# sensor.net
KiCad netlist of a schematic drawn in Altium Designer
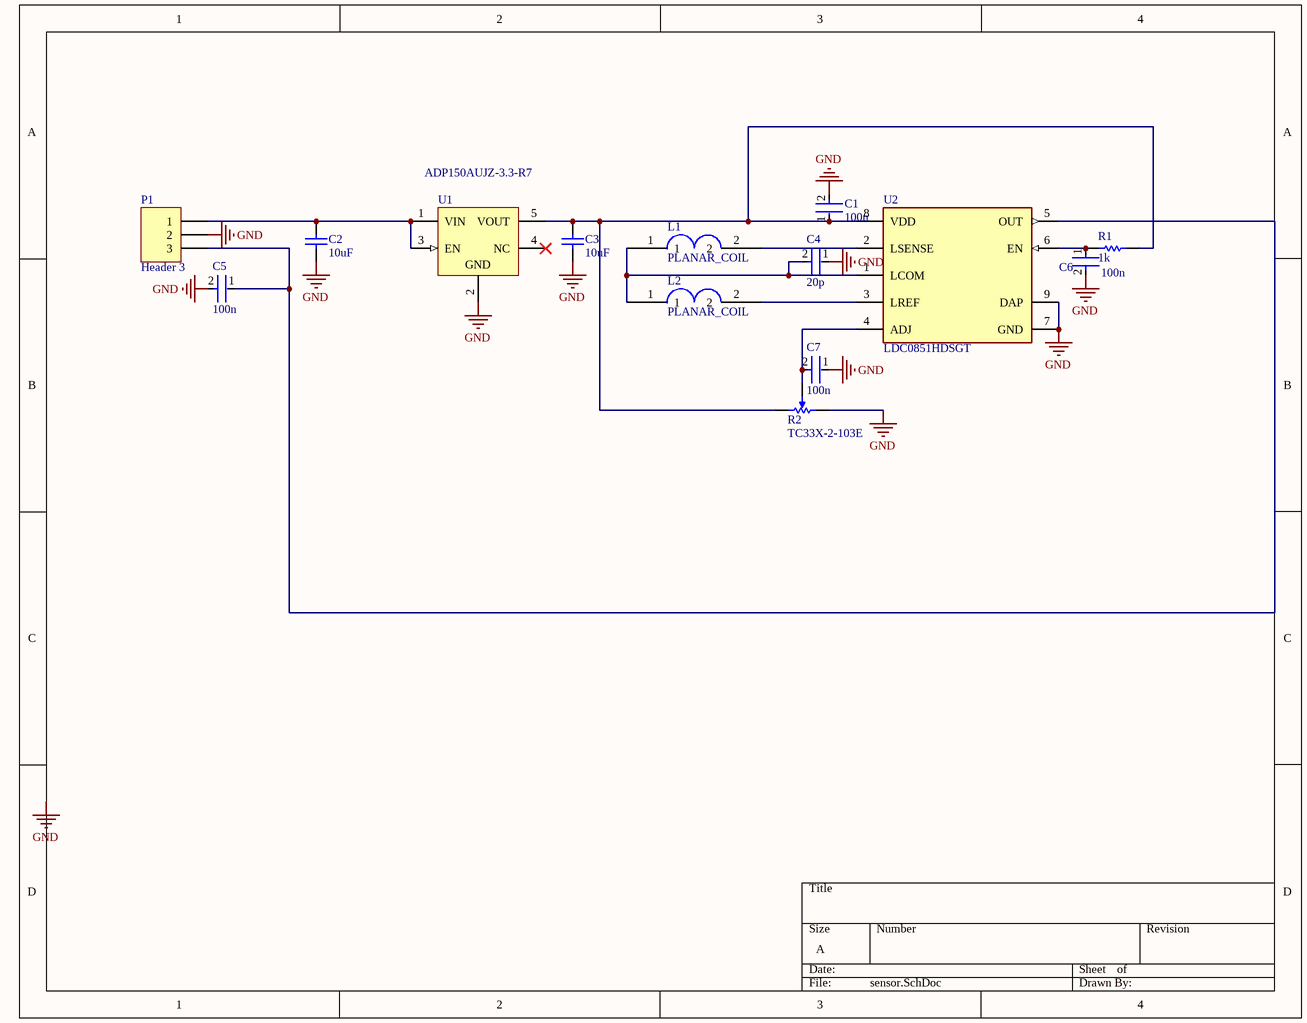
[diagram p0: sensor.SchDoc]

(export (version "E")
  (design (tool "Eeschema 10.0.6"))
  (components
    (comp (ref "C1")
      (value "100n")
      (footprint "FP-GRM15-MFG")
      (description "CAP CER 0.1UF 16V X7R 0402")
      (fields (field (name "MANUFACTURER PART NUMBER") "GRM155R71C104KA88D") (field (name "TOLERANCE") "10%"))
      (libsource (lib "Altium Content Vault") (part "236180d848d6139a670b325ea6854c9"))
    )
    (comp (ref "C2")
      (value "10uF")
      (footprint "CAPC2013X94X50ML20T25")
      (fields
        (field (name "MANUFACTURER") "AVX Interconnect / Elco")
        (field (name "PART NUMBER") "08051C104JAT2A")
      )
      (libsource (lib "Altium Content Vault") (part "CAP"))
    )
    (comp (ref "C3")
      (value "10uF")
      (footprint "CAPC2013X94X50ML20T25")
      (fields
        (field (name "MANUFACTURER") "AVX Interconnect / Elco")
        (field (name "PART NUMBER") "08051C104JAT2A")
      )
      (libsource (lib "Altium Content Vault") (part "CAP"))
    )
    (comp (ref "C4")
      (value "20p")
      (footprint "FP-GRM15-MFG")
      (description "CAP CER 0.1UF 16V X7R 0402")
      (fields (field (name "MANUFACTURER PART NUMBER") "GRM155R71C104KA88D") (field (name "TOLERANCE") "10%"))
      (libsource (lib "Altium Content Vault") (part "236180d848d6139a670b325ea6854c9"))
    )
    (comp (ref "C5")
      (value "100n")
      (footprint "FP-GRM15-MFG")
      (description "CAP CER 0.1UF 16V X7R 0402")
      (fields (field (name "MANUFACTURER PART NUMBER") "GRM155R71C104KA88D") (field (name "TOLERANCE") "10%"))
      (libsource (lib "Altium Content Vault") (part "236180d848d6139a670b325ea6854c9"))
    )
    (comp (ref "C6")
      (value "100n")
      (footprint "FP-GRM15-MFG")
      (description "CAP CER 0.1UF 16V X7R 0402")
      (fields (field (name "MANUFACTURER PART NUMBER") "GRM155R71C104KA88D") (field (name "TOLERANCE") "10%"))
      (libsource (lib "Altium Content Vault") (part "236180d848d6139a670b325ea6854c9"))
    )
    (comp (ref "C7")
      (value "100n")
      (footprint "FP-GRM15-MFG")
      (description "CAP CER 0.1UF 16V X7R 0402")
      (fields (field (name "MANUFACTURER PART NUMBER") "GRM155R71C104KA88D") (field (name "TOLERANCE") "10%"))
      (libsource (lib "Altium Content Vault") (part "236180d848d6139a670b325ea6854c9"))
    )
    (comp (ref "L1")
      (value "PLANAR_COIL")
      (footprint "PLANAR_INDUCTOR")
      (libsource (lib "planar_coil") (part "PLANAR_COIL"))
    )
    (comp (ref "L2")
      (value "PLANAR_COIL")
      (footprint "PLANAR_INDUCTOR")
      (libsource (lib "planar_coil") (part "PLANAR_COIL"))
    )
    (comp (ref "P1")
      (value "Header 3")
      (footprint "HDR1X3")
      (description "Header, 3-Pin")
      (fields (field (name "PUBLISHER") "Altium Limited"))
      (libsource (lib "Miscellaneous Connectors") (part "Header 3"))
    )
    (comp (ref "R1")
      (value "1k")
      (footprint "RESC1005X40X25NL05T10")
      (fields (field (name "MANUFACTURER") "Yageo / Phycomp") (field (name "PART NUMBER") "RC0402JR-070RL"))
      (libsource (lib "Altium Content Vault") (part "RES"))
    )
    (comp (ref "R2")
      (value "TC33X-2-103E")
      (footprint "BOUR-TC33X-2_V")
      (description "Trimming Potentiometer, 10000 Ohm, -40 to 100 degC, 3-Pin SMD, RoHS, Tape and Reel")
      (fields (field (name "TOLERANCE") "25%") (field (name "MANUFACTURER") "Bourns"))
      (libsource (lib "Altium Content Vault") (part "RES-ADJ-3_A"))
    )
    (comp (ref "U1")
      (value "ADP150AUJZ-3.3-R7")
      (footprint "ADI-UJ-5_M")
      (fields (field (name "MANUFACTURER") "Analog Devices"))
      (libsource (lib "Altium Content Vault") (part "ADI-ADP1XX-UJ-5"))
    )
    (comp (ref "U2")
      (value "LDC0851HDSGT")
      (footprint "FP-DSG0008A-MFG")
      (description "SENSOR PROX INDUCTIVE 8WFDFN")
      (libsource (lib "Altium Content Vault") (part "7aa8b213d4fc0aa2c2f3e23343721e9"))
    )
  )
  (nets
    (net (code "1") (name "GND") (class "Default")
      (node (ref "C1") (pin "2") (pinfunction "2_2") (pintype "passive"))
      (node (ref "C2") (pin "1") (pinfunction "1_1") (pintype "passive"))
      (node (ref "C3") (pin "1") (pinfunction "1_1") (pintype "passive"))
      (node (ref "C4") (pin "1") (pinfunction "1_1") (pintype "passive"))
      (node (ref "C5") (pin "2") (pinfunction "2_2") (pintype "passive"))
      (node (ref "C6") (pin "2") (pinfunction "2_2") (pintype "passive"))
      (node (ref "C7") (pin "1") (pinfunction "1_1") (pintype "passive"))
      (node (ref "P1") (pin "2") (pinfunction "2_2") (pintype "passive"))
      (node (ref "R2") (pin "1") (pinfunction "1_1") (pintype "passive"))
      (node (ref "U1") (pin "2") (pinfunction "GND_2") (pintype "power_in"))
      (node (ref "U2") (pin "7") (pinfunction "GND_7") (pintype "power_in"))
      (node (ref "U2") (pin "9") (pinfunction "DAP_9") (pintype "power_in"))
    )
    (net (code "2") (name "Net-(U1-EN)") (class "Default")
      (node (ref "C2") (pin "2") (pinfunction "2_2") (pintype "passive"))
      (node (ref "P1") (pin "1") (pinfunction "1_1") (pintype "passive"))
      (node (ref "U1") (pin "1") (pinfunction "VIN_1") (pintype "power_in"))
      (node (ref "U1") (pin "3") (pinfunction "EN_3") (pintype "input"))
    )
    (net (code "3") (name "Net-(U1-VOUT)") (class "Default")
      (node (ref "C1") (pin "1") (pinfunction "1_1") (pintype "passive"))
      (node (ref "C3") (pin "2") (pinfunction "2_2") (pintype "passive"))
      (node (ref "R1") (pin "2") (pinfunction "2_2") (pintype "passive"))
      (node (ref "R2") (pin "3") (pinfunction "3_3") (pintype "passive"))
      (node (ref "U1") (pin "5") (pinfunction "VOUT_5") (pintype "power_in"))
      (node (ref "U2") (pin "8") (pinfunction "VDD_8") (pintype "power_in"))
    )
    (net (code "4") (name "Net-(U2-ADJ)") (class "Default")
      (node (ref "C7") (pin "2") (pinfunction "2_2") (pintype "passive"))
      (node (ref "R2") (pin "2") (pinfunction "2_2") (pintype "passive"))
      (node (ref "U2") (pin "4") (pinfunction "ADJ_4") (pintype "passive"))
    )
    (net (code "5") (name "Net-(U2-EN)") (class "Default")
      (node (ref "C6") (pin "1") (pinfunction "1_1") (pintype "passive"))
      (node (ref "R1") (pin "1") (pinfunction "1_1") (pintype "passive"))
      (node (ref "U2") (pin "6") (pinfunction "EN_6") (pintype "input"))
    )
    (net (code "6") (name "Net-(U2-LCOM)") (class "Default")
      (node (ref "C4") (pin "2") (pinfunction "2_2") (pintype "passive"))
      (node (ref "L1") (pin "1") (pinfunction "1_1") (pintype "passive"))
      (node (ref "L2") (pin "1") (pinfunction "1_1") (pintype "passive"))
      (node (ref "U2") (pin "1") (pinfunction "LCOM_1") (pintype "passive"))
    )
    (net (code "7") (name "Net-(U2-LREF)") (class "Default")
      (node (ref "L2") (pin "2") (pinfunction "2_2") (pintype "passive"))
      (node (ref "U2") (pin "3") (pinfunction "LREF_3") (pintype "passive"))
    )
    (net (code "8") (name "Net-(U2-LSENSE)") (class "Default")
      (node (ref "L1") (pin "2") (pinfunction "2_2") (pintype "passive"))
      (node (ref "U2") (pin "2") (pinfunction "LSENSE_2") (pintype "passive"))
    )
    (net (code "9") (name "Net-(U2-OUT)") (class "Default")
      (node (ref "C5") (pin "1") (pinfunction "1_1") (pintype "passive"))
      (node (ref "P1") (pin "3") (pinfunction "3_3") (pintype "passive"))
      (node (ref "U2") (pin "5") (pinfunction "OUT_5") (pintype "output"))
    )
    (net (code "10") (name "unconnected-(U1-NC-Pad4)") (class "Default")
      (node (ref "U1") (pin "4") (pinfunction "NC_4") (pintype "passive+no_connect"))
    )
  )
)
